# led_2.net
KiCad netlist of a schematic drawn in EAGLE
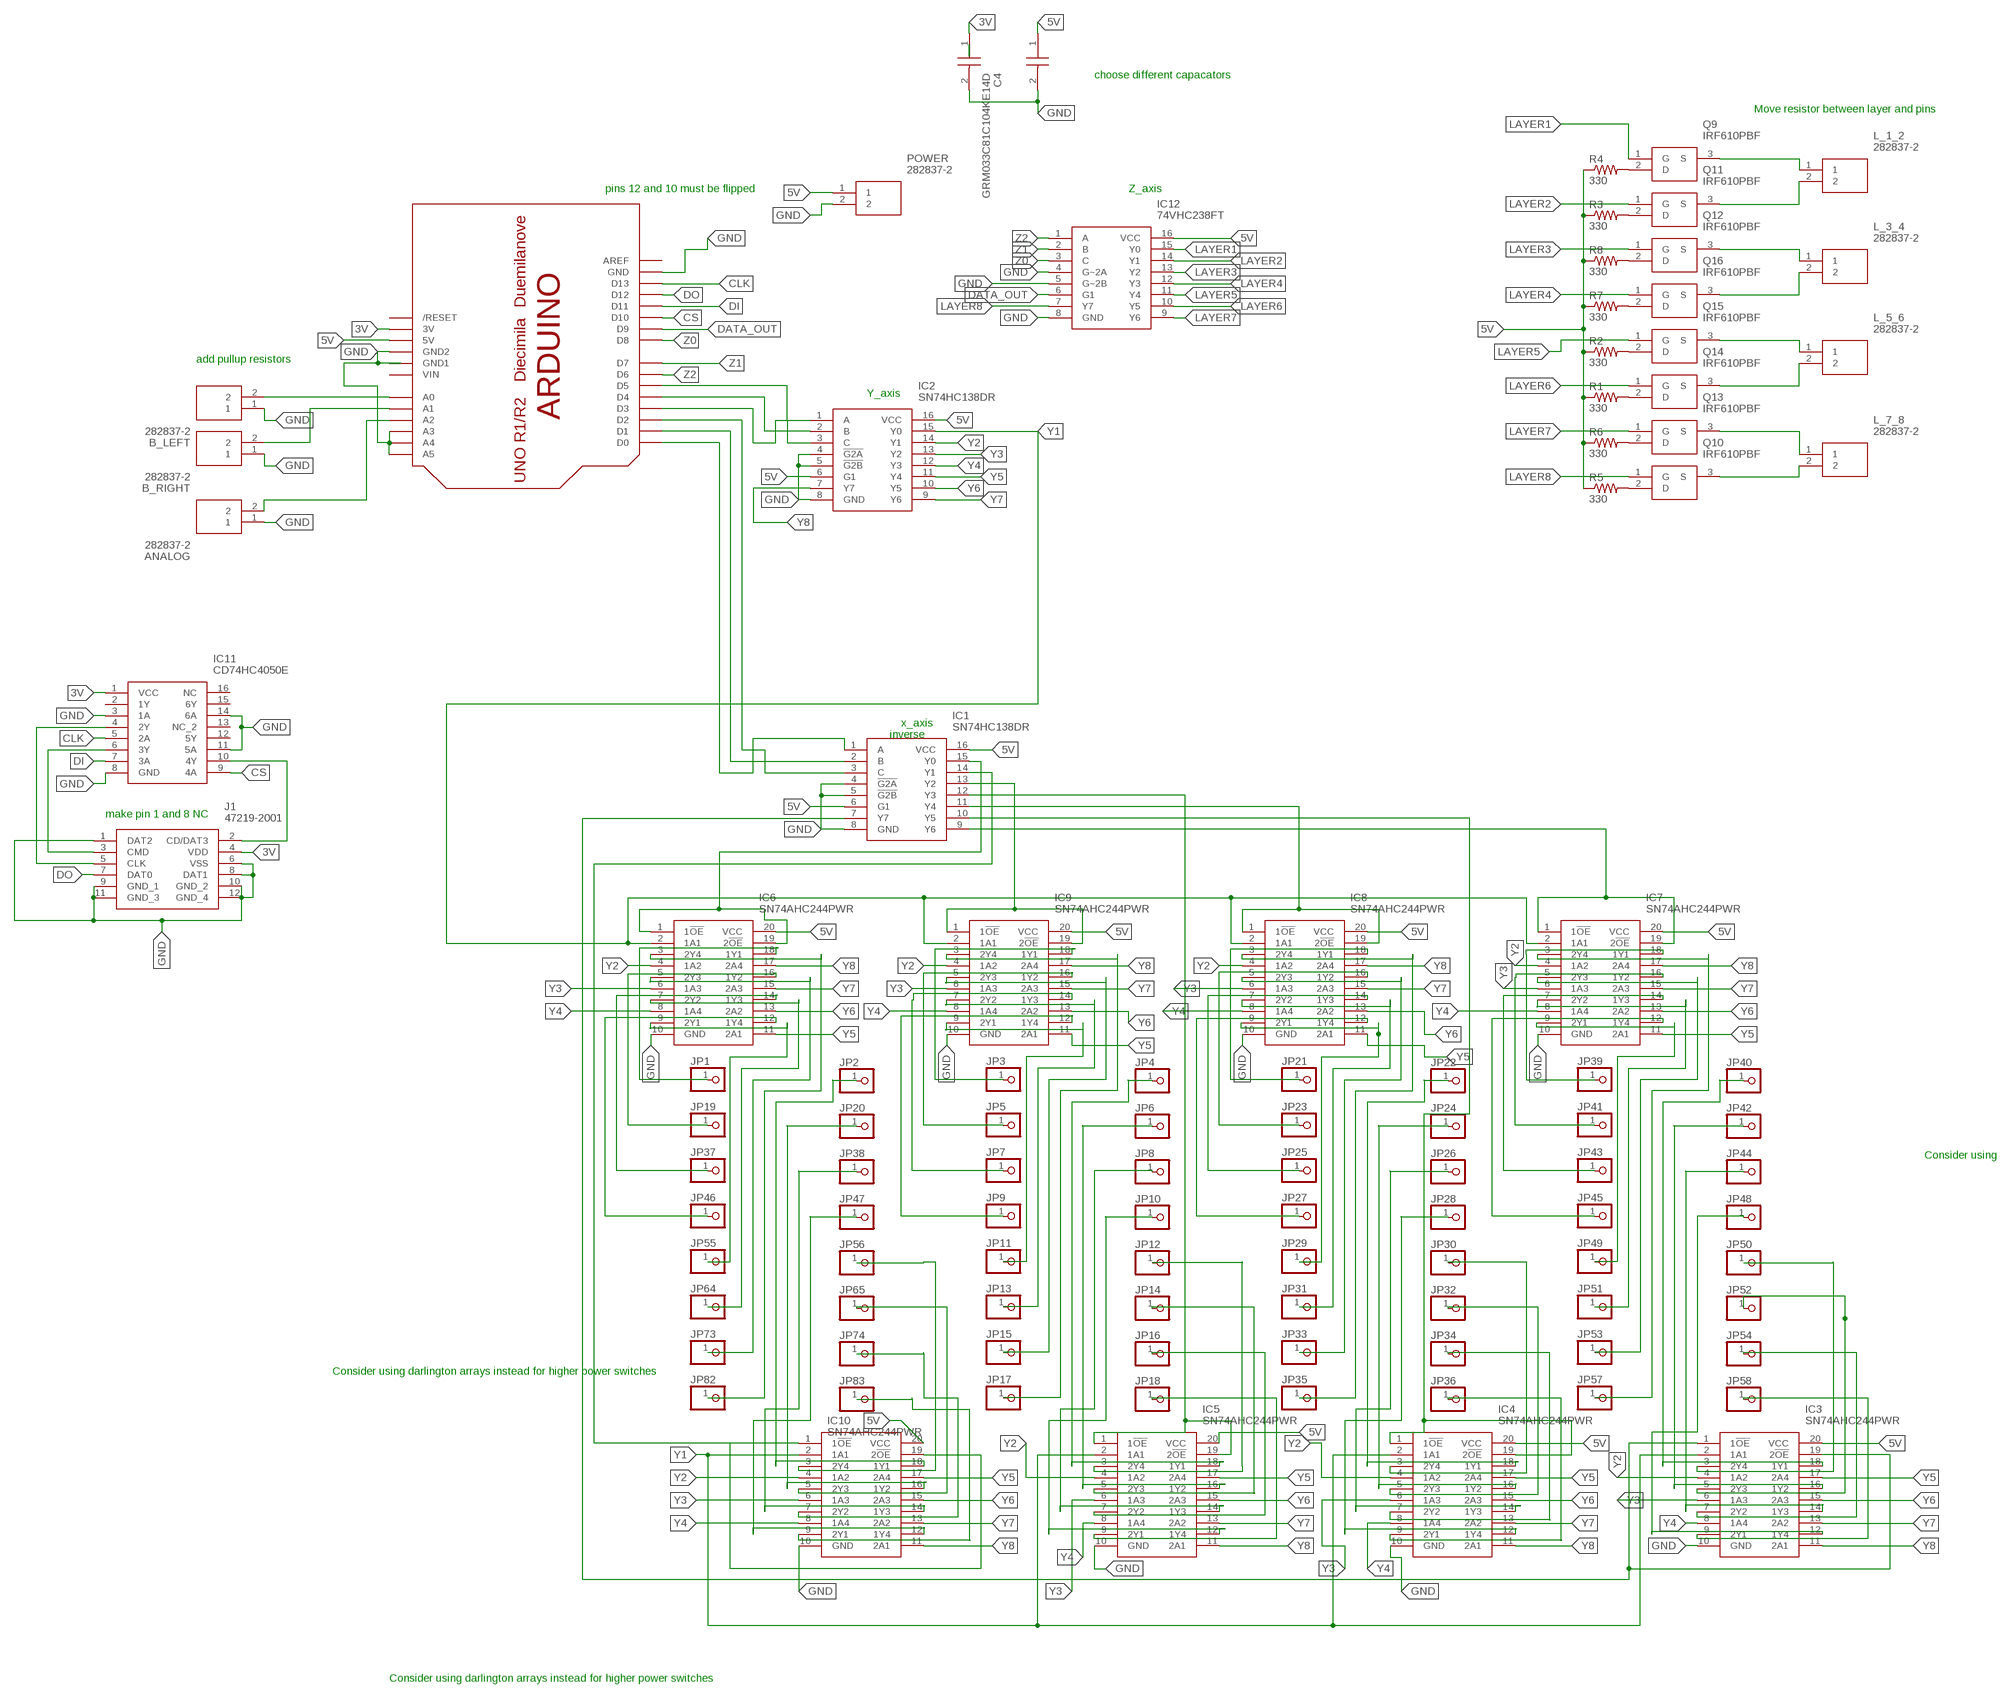
[diagram p0: schematic, sheet 1, part 1 of 2]
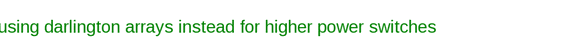
[diagram p1: schematic, sheet 1, part 2 of 2]

(export (version "E")
  (design (tool "Eeschema 10.0.6"))
  (components
    (comp (ref "ANALOG")
      (value "282837-2")
      (footprint "eagle-import:SHDR2W100P0X508_1X2_1016X820X1")
      (fields (field (name "MOUSER_PART_NUMBER") "571-2828372"))
      (libsource (lib "eagle-import") (part "282837-2"))
    )
    (comp (ref "B_LEFT")
      (value "282837-2")
      (footprint "eagle-import:SHDR2W100P0X508_1X2_1016X820X1")
      (fields (field (name "MOUSER_PART_NUMBER") "571-2828372"))
      (libsource (lib "eagle-import") (part "282837-2"))
    )
    (comp (ref "B_RIGHT")
      (value "282837-2")
      (footprint "eagle-import:SHDR2W100P0X508_1X2_1016X820X1")
      (fields (field (name "MOUSER_PART_NUMBER") "571-2828372"))
      (libsource (lib "eagle-import") (part "282837-2"))
    )
    (comp (ref "C4")
      (value "GRM033C81C104KE14D")
      (footprint "eagle-import:CAPC0603X33N")
      (fields (field (name "MOUSER_PART_NUMBER") "81-GRM033C81C104KE4D"))
      (libsource (lib "eagle-import") (part "GRM033C81C104KE14D"))
    )
    (comp (ref "C5")
      (value "GRM033C81C104KE14D")
      (footprint "eagle-import:CAPC0603X33N")
      (fields (field (name "MOUSER_PART_NUMBER") "81-GRM033C81C104KE4D"))
      (libsource (lib "eagle-import") (part "GRM033C81C104KE14D"))
    )
    (comp (ref "IC1")
      (value "SN74HC138DR")
      (footprint "eagle-import:SOIC127P600X175-16N")
      (fields (field (name "MOUSER_PART_NUMBER") "595-SN74HC138DR"))
      (libsource (lib "eagle-import") (part "SN74HC138DR"))
    )
    (comp (ref "IC2")
      (value "SN74HC138DR")
      (footprint "eagle-import:SOIC127P600X175-16N")
      (fields (field (name "MOUSER_PART_NUMBER") "595-SN74HC138DR"))
      (libsource (lib "eagle-import") (part "SN74HC138DR"))
    )
    (comp (ref "IC3")
      (value "SN74AHC244PWR")
      (footprint "eagle-import:SOP65P640X120-20N")
      (fields (field (name "MOUSER_PART_NUMBER") "595-SN74AHC244PWR"))
      (libsource (lib "eagle-import") (part "SN74AHC244PWR"))
    )
    (comp (ref "IC4")
      (value "SN74AHC244PWR")
      (footprint "eagle-import:SOP65P640X120-20N")
      (fields (field (name "MOUSER_PART_NUMBER") "595-SN74AHC244PWR"))
      (libsource (lib "eagle-import") (part "SN74AHC244PWR"))
    )
    (comp (ref "IC5")
      (value "SN74AHC244PWR")
      (footprint "eagle-import:SOP65P640X120-20N")
      (fields (field (name "MOUSER_PART_NUMBER") "595-SN74AHC244PWR"))
      (libsource (lib "eagle-import") (part "SN74AHC244PWR"))
    )
    (comp (ref "IC6")
      (value "SN74AHC244PWR")
      (footprint "eagle-import:SOP65P640X120-20N")
      (fields (field (name "MOUSER_PART_NUMBER") "595-SN74AHC244PWR"))
      (libsource (lib "eagle-import") (part "SN74AHC244PWR"))
    )
    (comp (ref "IC7")
      (value "SN74AHC244PWR")
      (footprint "eagle-import:SOP65P640X120-20N")
      (fields (field (name "MOUSER_PART_NUMBER") "595-SN74AHC244PWR"))
      (libsource (lib "eagle-import") (part "SN74AHC244PWR"))
    )
    (comp (ref "IC8")
      (value "SN74AHC244PWR")
      (footprint "eagle-import:SOP65P640X120-20N")
      (fields (field (name "MOUSER_PART_NUMBER") "595-SN74AHC244PWR"))
      (libsource (lib "eagle-import") (part "SN74AHC244PWR"))
    )
    (comp (ref "IC9")
      (value "SN74AHC244PWR")
      (footprint "eagle-import:SOP65P640X120-20N")
      (fields (field (name "MOUSER_PART_NUMBER") "595-SN74AHC244PWR"))
      (libsource (lib "eagle-import") (part "SN74AHC244PWR"))
    )
    (comp (ref "IC10")
      (value "SN74AHC244PWR")
      (footprint "eagle-import:SOP65P640X120-20N")
      (fields (field (name "MOUSER_PART_NUMBER") "595-SN74AHC244PWR"))
      (libsource (lib "eagle-import") (part "SN74AHC244PWR"))
    )
    (comp (ref "IC11")
      (value "CD74HC4050E")
      (footprint "eagle-import:DIP254P762X508-16")
      (fields (field (name "MOUSER_PART_NUMBER") "595-CD74HC4050E"))
      (libsource (lib "eagle-import") (part "CD74HC4050E"))
    )
    (comp (ref "IC12")
      (value "74VHC238FT")
      (footprint "eagle-import:SOP65P640X120-16N")
      (libsource (lib "eagle-import") (part "74VHC238FT"))
    )
    (comp (ref "J1")
      (value "47219-2001")
      (footprint "eagle-import:472192001")
      (fields (field (name "MOUSER_PART_NUMBER") "538-47219-2001"))
      (libsource (lib "eagle-import") (part "47219-2001"))
    )
    (comp (ref "JP1")
      (value "PINHD-1X1")
      (footprint "eagle-import:1X01")
      (libsource (lib "eagle-import") (part "PINHD-1X1"))
    )
    (comp (ref "JP2")
      (value "PINHD-1X1")
      (footprint "eagle-import:1X01")
      (libsource (lib "eagle-import") (part "PINHD-1X1"))
    )
    (comp (ref "JP3")
      (value "PINHD-1X1")
      (footprint "eagle-import:1X01")
      (libsource (lib "eagle-import") (part "PINHD-1X1"))
    )
    (comp (ref "JP4")
      (value "PINHD-1X1")
      (footprint "eagle-import:1X01")
      (libsource (lib "eagle-import") (part "PINHD-1X1"))
    )
    (comp (ref "JP5")
      (value "PINHD-1X1")
      (footprint "eagle-import:1X01")
      (libsource (lib "eagle-import") (part "PINHD-1X1"))
    )
    (comp (ref "JP6")
      (value "PINHD-1X1")
      (footprint "eagle-import:1X01")
      (libsource (lib "eagle-import") (part "PINHD-1X1"))
    )
    (comp (ref "JP7")
      (value "PINHD-1X1")
      (footprint "eagle-import:1X01")
      (libsource (lib "eagle-import") (part "PINHD-1X1"))
    )
    (comp (ref "JP8")
      (value "PINHD-1X1")
      (footprint "eagle-import:1X01")
      (libsource (lib "eagle-import") (part "PINHD-1X1"))
    )
    (comp (ref "JP9")
      (value "PINHD-1X1")
      (footprint "eagle-import:1X01")
      (libsource (lib "eagle-import") (part "PINHD-1X1"))
    )
    (comp (ref "JP10")
      (value "PINHD-1X1")
      (footprint "eagle-import:1X01")
      (libsource (lib "eagle-import") (part "PINHD-1X1"))
    )
    (comp (ref "JP11")
      (value "PINHD-1X1")
      (footprint "eagle-import:1X01")
      (libsource (lib "eagle-import") (part "PINHD-1X1"))
    )
    (comp (ref "JP12")
      (value "PINHD-1X1")
      (footprint "eagle-import:1X01")
      (libsource (lib "eagle-import") (part "PINHD-1X1"))
    )
    (comp (ref "JP13")
      (value "PINHD-1X1")
      (footprint "eagle-import:1X01")
      (libsource (lib "eagle-import") (part "PINHD-1X1"))
    )
    (comp (ref "JP14")
      (value "PINHD-1X1")
      (footprint "eagle-import:1X01")
      (libsource (lib "eagle-import") (part "PINHD-1X1"))
    )
    (comp (ref "JP15")
      (value "PINHD-1X1")
      (footprint "eagle-import:1X01")
      (libsource (lib "eagle-import") (part "PINHD-1X1"))
    )
    (comp (ref "JP16")
      (value "PINHD-1X1")
      (footprint "eagle-import:1X01")
      (libsource (lib "eagle-import") (part "PINHD-1X1"))
    )
    (comp (ref "JP17")
      (value "PINHD-1X1")
      (footprint "eagle-import:1X01")
      (libsource (lib "eagle-import") (part "PINHD-1X1"))
    )
    (comp (ref "JP18")
      (value "PINHD-1X1")
      (footprint "eagle-import:1X01")
      (libsource (lib "eagle-import") (part "PINHD-1X1"))
    )
    (comp (ref "JP19")
      (value "PINHD-1X1")
      (footprint "eagle-import:1X01")
      (libsource (lib "eagle-import") (part "PINHD-1X1"))
    )
    (comp (ref "JP20")
      (value "PINHD-1X1")
      (footprint "eagle-import:1X01")
      (libsource (lib "eagle-import") (part "PINHD-1X1"))
    )
    (comp (ref "JP21")
      (value "PINHD-1X1")
      (footprint "eagle-import:1X01")
      (libsource (lib "eagle-import") (part "PINHD-1X1"))
    )
    (comp (ref "JP22")
      (value "PINHD-1X1")
      (footprint "eagle-import:1X01")
      (libsource (lib "eagle-import") (part "PINHD-1X1"))
    )
    (comp (ref "JP23")
      (value "PINHD-1X1")
      (footprint "eagle-import:1X01")
      (libsource (lib "eagle-import") (part "PINHD-1X1"))
    )
    (comp (ref "JP24")
      (value "PINHD-1X1")
      (footprint "eagle-import:1X01")
      (libsource (lib "eagle-import") (part "PINHD-1X1"))
    )
    (comp (ref "JP25")
      (value "PINHD-1X1")
      (footprint "eagle-import:1X01")
      (libsource (lib "eagle-import") (part "PINHD-1X1"))
    )
    (comp (ref "JP26")
      (value "PINHD-1X1")
      (footprint "eagle-import:1X01")
      (libsource (lib "eagle-import") (part "PINHD-1X1"))
    )
    (comp (ref "JP27")
      (value "PINHD-1X1")
      (footprint "eagle-import:1X01")
      (libsource (lib "eagle-import") (part "PINHD-1X1"))
    )
    (comp (ref "JP28")
      (value "PINHD-1X1")
      (footprint "eagle-import:1X01")
      (libsource (lib "eagle-import") (part "PINHD-1X1"))
    )
    (comp (ref "JP29")
      (value "PINHD-1X1")
      (footprint "eagle-import:1X01")
      (libsource (lib "eagle-import") (part "PINHD-1X1"))
    )
    (comp (ref "JP30")
      (value "PINHD-1X1")
      (footprint "eagle-import:1X01")
      (libsource (lib "eagle-import") (part "PINHD-1X1"))
    )
    (comp (ref "JP31")
      (value "PINHD-1X1")
      (footprint "eagle-import:1X01")
      (libsource (lib "eagle-import") (part "PINHD-1X1"))
    )
    (comp (ref "JP32")
      (value "PINHD-1X1")
      (footprint "eagle-import:1X01")
      (libsource (lib "eagle-import") (part "PINHD-1X1"))
    )
    (comp (ref "JP33")
      (value "PINHD-1X1")
      (footprint "eagle-import:1X01")
      (libsource (lib "eagle-import") (part "PINHD-1X1"))
    )
    (comp (ref "JP34")
      (value "PINHD-1X1")
      (footprint "eagle-import:1X01")
      (libsource (lib "eagle-import") (part "PINHD-1X1"))
    )
    (comp (ref "JP35")
      (value "PINHD-1X1")
      (footprint "eagle-import:1X01")
      (libsource (lib "eagle-import") (part "PINHD-1X1"))
    )
    (comp (ref "JP36")
      (value "PINHD-1X1")
      (footprint "eagle-import:1X01")
      (libsource (lib "eagle-import") (part "PINHD-1X1"))
    )
    (comp (ref "JP37")
      (value "PINHD-1X1")
      (footprint "eagle-import:1X01")
      (libsource (lib "eagle-import") (part "PINHD-1X1"))
    )
    (comp (ref "JP38")
      (value "PINHD-1X1")
      (footprint "eagle-import:1X01")
      (libsource (lib "eagle-import") (part "PINHD-1X1"))
    )
    (comp (ref "JP39")
      (value "PINHD-1X1")
      (footprint "eagle-import:1X01")
      (libsource (lib "eagle-import") (part "PINHD-1X1"))
    )
    (comp (ref "JP40")
      (value "PINHD-1X1")
      (footprint "eagle-import:1X01")
      (libsource (lib "eagle-import") (part "PINHD-1X1"))
    )
    (comp (ref "JP41")
      (value "PINHD-1X1")
      (footprint "eagle-import:1X01")
      (libsource (lib "eagle-import") (part "PINHD-1X1"))
    )
    (comp (ref "JP42")
      (value "PINHD-1X1")
      (footprint "eagle-import:1X01")
      (libsource (lib "eagle-import") (part "PINHD-1X1"))
    )
    (comp (ref "JP43")
      (value "PINHD-1X1")
      (footprint "eagle-import:1X01")
      (libsource (lib "eagle-import") (part "PINHD-1X1"))
    )
    (comp (ref "JP44")
      (value "PINHD-1X1")
      (footprint "eagle-import:1X01")
      (libsource (lib "eagle-import") (part "PINHD-1X1"))
    )
    (comp (ref "JP45")
      (value "PINHD-1X1")
      (footprint "eagle-import:1X01")
      (libsource (lib "eagle-import") (part "PINHD-1X1"))
    )
    (comp (ref "JP46")
      (value "PINHD-1X1")
      (footprint "eagle-import:1X01")
      (libsource (lib "eagle-import") (part "PINHD-1X1"))
    )
    (comp (ref "JP47")
      (value "PINHD-1X1")
      (footprint "eagle-import:1X01")
      (libsource (lib "eagle-import") (part "PINHD-1X1"))
    )
    (comp (ref "JP48")
      (value "PINHD-1X1")
      (footprint "eagle-import:1X01")
      (libsource (lib "eagle-import") (part "PINHD-1X1"))
    )
    (comp (ref "JP49")
      (value "PINHD-1X1")
      (footprint "eagle-import:1X01")
      (libsource (lib "eagle-import") (part "PINHD-1X1"))
    )
    (comp (ref "JP50")
      (value "PINHD-1X1")
      (footprint "eagle-import:1X01")
      (libsource (lib "eagle-import") (part "PINHD-1X1"))
    )
    (comp (ref "JP51")
      (value "PINHD-1X1")
      (footprint "eagle-import:1X01")
      (libsource (lib "eagle-import") (part "PINHD-1X1"))
    )
    (comp (ref "JP52")
      (value "PINHD-1X1")
      (footprint "eagle-import:1X01")
      (libsource (lib "eagle-import") (part "PINHD-1X1"))
    )
    (comp (ref "JP53")
      (value "PINHD-1X1")
      (footprint "eagle-import:1X01")
      (libsource (lib "eagle-import") (part "PINHD-1X1"))
    )
    (comp (ref "JP54")
      (value "PINHD-1X1")
      (footprint "eagle-import:1X01")
      (libsource (lib "eagle-import") (part "PINHD-1X1"))
    )
    (comp (ref "JP55")
      (value "PINHD-1X1")
      (footprint "eagle-import:1X01")
      (libsource (lib "eagle-import") (part "PINHD-1X1"))
    )
    (comp (ref "JP56")
      (value "PINHD-1X1")
      (footprint "eagle-import:1X01")
      (libsource (lib "eagle-import") (part "PINHD-1X1"))
    )
    (comp (ref "JP57")
      (value "PINHD-1X1")
      (footprint "eagle-import:1X01")
      (libsource (lib "eagle-import") (part "PINHD-1X1"))
    )
    (comp (ref "JP58")
      (value "PINHD-1X1")
      (footprint "eagle-import:1X01")
      (libsource (lib "eagle-import") (part "PINHD-1X1"))
    )
    (comp (ref "JP64")
      (value "PINHD-1X1")
      (footprint "eagle-import:1X01")
      (libsource (lib "eagle-import") (part "PINHD-1X1"))
    )
    (comp (ref "JP65")
      (value "PINHD-1X1")
      (footprint "eagle-import:1X01")
      (libsource (lib "eagle-import") (part "PINHD-1X1"))
    )
    (comp (ref "JP73")
      (value "PINHD-1X1")
      (footprint "eagle-import:1X01")
      (libsource (lib "eagle-import") (part "PINHD-1X1"))
    )
    (comp (ref "JP74")
      (value "PINHD-1X1")
      (footprint "eagle-import:1X01")
      (libsource (lib "eagle-import") (part "PINHD-1X1"))
    )
    (comp (ref "JP82")
      (value "PINHD-1X1")
      (footprint "eagle-import:1X01")
      (libsource (lib "eagle-import") (part "PINHD-1X1"))
    )
    (comp (ref "JP83")
      (value "PINHD-1X1")
      (footprint "eagle-import:1X01")
      (libsource (lib "eagle-import") (part "PINHD-1X1"))
    )
    (comp (ref "L_1_2")
      (value "282837-2")
      (footprint "eagle-import:SHDR2W100P0X508_1X2_1016X820X1")
      (fields (field (name "MOUSER_PART_NUMBER") "571-2828372"))
      (libsource (lib "eagle-import") (part "282837-2"))
    )
    (comp (ref "L_3_4")
      (value "282837-2")
      (footprint "eagle-import:SHDR2W100P0X508_1X2_1016X820X1")
      (fields (field (name "MOUSER_PART_NUMBER") "571-2828372"))
      (libsource (lib "eagle-import") (part "282837-2"))
    )
    (comp (ref "L_5_6")
      (value "282837-2")
      (footprint "eagle-import:SHDR2W100P0X508_1X2_1016X820X1")
      (fields (field (name "MOUSER_PART_NUMBER") "571-2828372"))
      (libsource (lib "eagle-import") (part "282837-2"))
    )
    (comp (ref "L_7_8")
      (value "282837-2")
      (footprint "eagle-import:SHDR2W100P0X508_1X2_1016X820X1")
      (fields (field (name "MOUSER_PART_NUMBER") "571-2828372"))
      (libsource (lib "eagle-import") (part "282837-2"))
    )
    (comp (ref "POWER")
      (value "282837-2")
      (footprint "eagle-import:SHDR2W100P0X508_1X2_1016X820X1")
      (fields (field (name "MOUSER_PART_NUMBER") "571-2828372"))
      (libsource (lib "eagle-import") (part "282837-2"))
    )
    (comp (ref "Q9")
      (value "IRF610PBF")
      (footprint "eagle-import:TO254P465X1024X2050-3P")
      (fields (field (name "MOUSER_PART_NUMBER") "844-IRF610PBF"))
      (libsource (lib "eagle-import") (part "IRF610PBF"))
    )
    (comp (ref "Q10")
      (value "IRF610PBF")
      (footprint "eagle-import:TO254P465X1024X2050-3P")
      (fields (field (name "MOUSER_PART_NUMBER") "844-IRF610PBF"))
      (libsource (lib "eagle-import") (part "IRF610PBF"))
    )
    (comp (ref "Q11")
      (value "IRF610PBF")
      (footprint "eagle-import:TO254P465X1024X2050-3P")
      (fields (field (name "MOUSER_PART_NUMBER") "844-IRF610PBF"))
      (libsource (lib "eagle-import") (part "IRF610PBF"))
    )
    (comp (ref "Q12")
      (value "IRF610PBF")
      (footprint "eagle-import:TO254P465X1024X2050-3P")
      (fields (field (name "MOUSER_PART_NUMBER") "844-IRF610PBF"))
      (libsource (lib "eagle-import") (part "IRF610PBF"))
    )
    (comp (ref "Q13")
      (value "IRF610PBF")
      (footprint "eagle-import:TO254P465X1024X2050-3P")
      (fields (field (name "MOUSER_PART_NUMBER") "844-IRF610PBF"))
      (libsource (lib "eagle-import") (part "IRF610PBF"))
    )
    (comp (ref "Q14")
      (value "IRF610PBF")
      (footprint "eagle-import:TO254P465X1024X2050-3P")
      (fields (field (name "MOUSER_PART_NUMBER") "844-IRF610PBF"))
      (libsource (lib "eagle-import") (part "IRF610PBF"))
    )
    (comp (ref "Q15")
      (value "IRF610PBF")
      (footprint "eagle-import:TO254P465X1024X2050-3P")
      (fields (field (name "MOUSER_PART_NUMBER") "844-IRF610PBF"))
      (libsource (lib "eagle-import") (part "IRF610PBF"))
    )
    (comp (ref "Q16")
      (value "IRF610PBF")
      (footprint "eagle-import:TO254P465X1024X2050-3P")
      (fields (field (name "MOUSER_PART_NUMBER") "844-IRF610PBF"))
      (libsource (lib "eagle-import") (part "IRF610PBF"))
    )
    (comp (ref "R1")
      (value "330")
      (footprint "eagle-import:0207_12")
      (libsource (lib "eagle-import") (part "R-US_0207/12"))
    )
    (comp (ref "R2")
      (value "330")
      (footprint "eagle-import:0207_12")
      (libsource (lib "eagle-import") (part "R-US_0207/12"))
    )
    (comp (ref "R3")
      (value "330")
      (footprint "eagle-import:0207_12")
      (libsource (lib "eagle-import") (part "R-US_0207/12"))
    )
    (comp (ref "R4")
      (value "330")
      (footprint "eagle-import:0207_12")
      (libsource (lib "eagle-import") (part "R-US_0207/12"))
    )
    (comp (ref "R5")
      (value "330")
      (footprint "eagle-import:0207_12")
      (libsource (lib "eagle-import") (part "R-US_0207/12"))
    )
    (comp (ref "R6")
      (value "330")
      (footprint "eagle-import:0207_12")
      (libsource (lib "eagle-import") (part "R-US_0207/12"))
    )
    (comp (ref "R7")
      (value "330")
      (footprint "eagle-import:0207_12")
      (libsource (lib "eagle-import") (part "R-US_0207/12"))
    )
    (comp (ref "R8")
      (value "330")
      (footprint "eagle-import:0207_12")
      (libsource (lib "eagle-import") (part "R-US_0207/12"))
    )
    (comp (ref "U$2")
      (value "ARDUINO-NOHOLE")
      (footprint "eagle-import:ARDUINO-NOHOLE")
      (libsource (lib "eagle-import") (part "ARDUINO-NOHOLE"))
    )
  )
  (nets
    (net (code "1") (name "/VIN") (class "Default")
      (node (ref "U$2") (pin "VIN") (pinfunction "VIN_VIN") (pintype "power_in"))
    )
    (net (code "2") (name "3V") (class "Default")
      (node (ref "C4") (pin "1") (pinfunction "1_1") (pintype "bidirectional"))
      (node (ref "IC11") (pin "1") (pinfunction "VCC_1") (pintype "bidirectional"))
      (node (ref "J1") (pin "4") (pinfunction "VDD_4") (pintype "bidirectional"))
      (node (ref "U$2") (pin "3V") (pinfunction "3V_3V") (pintype "power_in"))
    )
    (net (code "3") (name "5V") (class "Default")
      (node (ref "C5") (pin "1") (pinfunction "1_1") (pintype "bidirectional"))
      (node (ref "IC1") (pin "16") (pinfunction "VCC_16") (pintype "power_in"))
      (node (ref "IC1") (pin "6") (pinfunction "G1_6") (pintype "bidirectional"))
      (node (ref "IC10") (pin "20") (pinfunction "VCC_20") (pintype "bidirectional"))
      (node (ref "IC12") (pin "16") (pinfunction "VCC_16") (pintype "power_in"))
      (node (ref "IC2") (pin "16") (pinfunction "VCC_16") (pintype "power_in"))
      (node (ref "IC2") (pin "6") (pinfunction "G1_6") (pintype "bidirectional"))
      (node (ref "IC3") (pin "20") (pinfunction "VCC_20") (pintype "bidirectional"))
      (node (ref "IC4") (pin "20") (pinfunction "VCC_20") (pintype "bidirectional"))
      (node (ref "IC5") (pin "20") (pinfunction "VCC_20") (pintype "bidirectional"))
      (node (ref "IC6") (pin "20") (pinfunction "VCC_20") (pintype "bidirectional"))
      (node (ref "IC7") (pin "20") (pinfunction "VCC_20") (pintype "bidirectional"))
      (node (ref "IC8") (pin "20") (pinfunction "VCC_20") (pintype "bidirectional"))
      (node (ref "IC9") (pin "20") (pinfunction "VCC_20") (pintype "bidirectional"))
      (node (ref "POWER") (pin "1") (pinfunction "1_1") (pintype "bidirectional"))
      (node (ref "R1") (pin "1") (pinfunction "1_1") (pintype "passive"))
      (node (ref "R2") (pin "1") (pinfunction "1_1") (pintype "passive"))
      (node (ref "R3") (pin "1") (pinfunction "1_1") (pintype "passive"))
      (node (ref "R4") (pin "1") (pinfunction "1_1") (pintype "passive"))
      (node (ref "R5") (pin "1") (pinfunction "1_1") (pintype "passive"))
      (node (ref "R6") (pin "1") (pinfunction "1_1") (pintype "passive"))
      (node (ref "R7") (pin "1") (pinfunction "1_1") (pintype "passive"))
      (node (ref "R8") (pin "1") (pinfunction "1_1") (pintype "passive"))
      (node (ref "U$2") (pin "5V") (pinfunction "5V_5V") (pintype "power_in"))
    )
    (net (code "4") (name "CLK") (class "Default")
      (node (ref "IC11") (pin "5") (pinfunction "2A_5") (pintype "bidirectional"))
      (node (ref "U$2") (pin "D13") (pinfunction "D13_D13") (pintype "bidirectional"))
    )
    (net (code "5") (name "CS") (class "Default")
      (node (ref "IC11") (pin "9") (pinfunction "4A_9") (pintype "bidirectional"))
      (node (ref "U$2") (pin "D10") (pinfunction "D10_D10") (pintype "bidirectional"))
    )
    (net (code "6") (name "DATA_OUT") (class "Default")
      (node (ref "IC12") (pin "6") (pinfunction "G1_6") (pintype "input"))
      (node (ref "U$2") (pin "D9") (pinfunction "D9_D9") (pintype "bidirectional"))
    )
    (net (code "7") (name "DI") (class "Default")
      (node (ref "IC11") (pin "7") (pinfunction "3A_7") (pintype "bidirectional"))
      (node (ref "U$2") (pin "D11") (pinfunction "D11_D11") (pintype "bidirectional"))
    )
    (net (code "8") (name "DO") (class "Default")
      (node (ref "J1") (pin "7") (pinfunction "DAT0_7") (pintype "bidirectional"))
      (node (ref "U$2") (pin "D12") (pinfunction "D12_D12") (pintype "bidirectional"))
    )
    (net (code "9") (name "GND") (class "Default")
      (node (ref "ANALOG") (pin "1") (pinfunction "1_1") (pintype "bidirectional"))
      (node (ref "B_LEFT") (pin "1") (pinfunction "1_1") (pintype "bidirectional"))
      (node (ref "B_RIGHT") (pin "1") (pinfunction "1_1") (pintype "bidirectional"))
      (node (ref "C4") (pin "2") (pinfunction "2_2") (pintype "bidirectional"))
      (node (ref "C5") (pin "2") (pinfunction "2_2") (pintype "bidirectional"))
      (node (ref "IC1") (pin "4") (pinfunction "~{G2A}_4") (pintype "bidirectional"))
      (node (ref "IC1") (pin "5") (pinfunction "~{G2B}_5") (pintype "bidirectional"))
      (node (ref "IC1") (pin "8") (pinfunction "GND_8") (pintype "power_in"))
      (node (ref "IC10") (pin "10") (pinfunction "GND_10") (pintype "bidirectional"))
      (node (ref "IC11") (pin "11") (pinfunction "5A_11") (pintype "bidirectional"))
      (node (ref "IC11") (pin "14") (pinfunction "6A_14") (pintype "bidirectional"))
      (node (ref "IC11") (pin "3") (pinfunction "1A_3") (pintype "bidirectional"))
      (node (ref "IC11") (pin "8") (pinfunction "GND_8") (pintype "bidirectional"))
      (node (ref "IC12") (pin "4") (pinfunction "G~{2A}_4") (pintype "input"))
      (node (ref "IC12") (pin "5") (pinfunction "G~{2B}_5") (pintype "input"))
      (node (ref "IC12") (pin "8") (pinfunction "GND_8") (pintype "power_in"))
      (node (ref "IC2") (pin "4") (pinfunction "~{G2A}_4") (pintype "bidirectional"))
      (node (ref "IC2") (pin "5") (pinfunction "~{G2B}_5") (pintype "bidirectional"))
      (node (ref "IC2") (pin "8") (pinfunction "GND_8") (pintype "power_in"))
      (node (ref "IC3") (pin "10") (pinfunction "GND_10") (pintype "bidirectional"))
      (node (ref "IC4") (pin "10") (pinfunction "GND_10") (pintype "bidirectional"))
      (node (ref "IC5") (pin "10") (pinfunction "GND_10") (pintype "bidirectional"))
      (node (ref "IC6") (pin "10") (pinfunction "GND_10") (pintype "bidirectional"))
      (node (ref "IC7") (pin "10") (pinfunction "GND_10") (pintype "bidirectional"))
      (node (ref "IC8") (pin "10") (pinfunction "GND_10") (pintype "bidirectional"))
      (node (ref "IC9") (pin "10") (pinfunction "GND_10") (pintype "bidirectional"))
      (node (ref "J1") (pin "1") (pinfunction "DAT2_1") (pintype "bidirectional"))
      (node (ref "J1") (pin "10") (pinfunction "GND_2_10") (pintype "bidirectional"))
      (node (ref "J1") (pin "11") (pinfunction "GND_3_11") (pintype "bidirectional"))
      (node (ref "J1") (pin "12") (pinfunction "GND_4_12") (pintype "bidirectional"))
      (node (ref "J1") (pin "6") (pinfunction "VSS_6") (pintype "bidirectional"))
      (node (ref "J1") (pin "8") (pinfunction "DAT1_8") (pintype "bidirectional"))
      (node (ref "J1") (pin "9") (pinfunction "GND_1_9") (pintype "bidirectional"))
      (node (ref "POWER") (pin "2") (pinfunction "2_2") (pintype "bidirectional"))
      (node (ref "U$2") (pin "A3") (pinfunction "A3_A3") (pintype "bidirectional"))
      (node (ref "U$2") (pin "A4") (pinfunction "A4_A4") (pintype "bidirectional"))
      (node (ref "U$2") (pin "A5") (pinfunction "A5_A5") (pintype "bidirectional"))
      (node (ref "U$2") (pin "GND") (pinfunction "GND_GND") (pintype "power_in"))
      (node (ref "U$2") (pin "GND1") (pinfunction "GND1_GND1") (pintype "power_in"))
      (node (ref "U$2") (pin "GND2") (pinfunction "GND2_GND2") (pintype "power_in"))
    )
    (net (code "10") (name "LAYER1") (class "Default")
      (node (ref "IC12") (pin "15") (pinfunction "Y0_15") (pintype "output"))
      (node (ref "Q9") (pin "1") (pinfunction "G_1") (pintype "bidirectional"))
    )
    (net (code "11") (name "LAYER2") (class "Default")
      (node (ref "IC12") (pin "14") (pinfunction "Y1_14") (pintype "output"))
      (node (ref "Q11") (pin "1") (pinfunction "G_1") (pintype "bidirectional"))
    )
    (net (code "12") (name "LAYER3") (class "Default")
      (node (ref "IC12") (pin "13") (pinfunction "Y2_13") (pintype "output"))
      (node (ref "Q12") (pin "1") (pinfunction "G_1") (pintype "bidirectional"))
    )
    (net (code "13") (name "LAYER4") (class "Default")
      (node (ref "IC12") (pin "12") (pinfunction "Y3_12") (pintype "output"))
      (node (ref "Q16") (pin "1") (pinfunction "G_1") (pintype "bidirectional"))
    )
    (net (code "14") (name "LAYER5") (class "Default")
      (node (ref "IC12") (pin "11") (pinfunction "Y4_11") (pintype "output"))
      (node (ref "Q15") (pin "1") (pinfunction "G_1") (pintype "bidirectional"))
    )
    (net (code "15") (name "LAYER6") (class "Default")
      (node (ref "IC12") (pin "10") (pinfunction "Y5_10") (pintype "output"))
      (node (ref "Q14") (pin "1") (pinfunction "G_1") (pintype "bidirectional"))
    )
    (net (code "16") (name "LAYER7") (class "Default")
      (node (ref "IC12") (pin "9") (pinfunction "Y6_9") (pintype "output"))
      (node (ref "Q13") (pin "1") (pinfunction "G_1") (pintype "bidirectional"))
    )
    (net (code "17") (name "LAYER8") (class "Default")
      (node (ref "IC12") (pin "7") (pinfunction "Y7_7") (pintype "output"))
      (node (ref "Q10") (pin "1") (pinfunction "G_1") (pintype "bidirectional"))
    )
    (net (code "18") (name "Net-(ANALOG-Pad2)") (class "Default")
      (node (ref "ANALOG") (pin "2") (pinfunction "2_2") (pintype "bidirectional"))
      (node (ref "U$2") (pin "A2") (pinfunction "A2_A2") (pintype "bidirectional"))
    )
    (net (code "19") (name "Net-(B_LEFT-Pad2)") (class "Default")
      (node (ref "B_LEFT") (pin "2") (pinfunction "2_2") (pintype "bidirectional"))
      (node (ref "U$2") (pin "A0") (pinfunction "A0_A0") (pintype "bidirectional"))
    )
    (net (code "20") (name "Net-(B_RIGHT-Pad2)") (class "Default")
      (node (ref "B_RIGHT") (pin "2") (pinfunction "2_2") (pintype "bidirectional"))
      (node (ref "U$2") (pin "A1") (pinfunction "A1_A1") (pintype "bidirectional"))
    )
    (net (code "21") (name "Net-(IC1-A)") (class "Default")
      (node (ref "IC1") (pin "1") (pinfunction "A_1") (pintype "bidirectional"))
      (node (ref "U$2") (pin "D0") (pinfunction "D0_D0") (pintype "bidirectional"))
    )
    (net (code "22") (name "Net-(IC1-B)") (class "Default")
      (node (ref "IC1") (pin "2") (pinfunction "B_2") (pintype "bidirectional"))
      (node (ref "U$2") (pin "D1") (pinfunction "D1_D1") (pintype "bidirectional"))
    )
    (net (code "23") (name "Net-(IC1-C)") (class "Default")
      (node (ref "IC1") (pin "3") (pinfunction "C_3") (pintype "bidirectional"))
      (node (ref "U$2") (pin "D2") (pinfunction "D2_D2") (pintype "bidirectional"))
    )
    (net (code "24") (name "Net-(IC1-Y0)") (class "Default")
      (node (ref "IC1") (pin "15") (pinfunction "Y0_15") (pintype "bidirectional"))
      (node (ref "IC6") (pin "1") (pinfunction "1~{OE}_1") (pintype "bidirectional"))
      (node (ref "IC6") (pin "19") (pinfunction "2~{OE}_19") (pintype "bidirectional"))
    )
    (net (code "25") (name "Net-(IC1-Y1)") (class "Default")
      (node (ref "IC1") (pin "14") (pinfunction "Y1_14") (pintype "bidirectional"))
      (node (ref "IC10") (pin "1") (pinfunction "1~{OE}_1") (pintype "bidirectional"))
      (node (ref "IC10") (pin "19") (pinfunction "2~{OE}_19") (pintype "bidirectional"))
    )
    (net (code "26") (name "Net-(IC1-Y2)") (class "Default")
      (node (ref "IC1") (pin "13") (pinfunction "Y2_13") (pintype "bidirectional"))
      (node (ref "IC9") (pin "1") (pinfunction "1~{OE}_1") (pintype "bidirectional"))
      (node (ref "IC9") (pin "19") (pinfunction "2~{OE}_19") (pintype "bidirectional"))
    )
    (net (code "27") (name "Net-(IC1-Y3)") (class "Default")
      (node (ref "IC1") (pin "12") (pinfunction "Y3_12") (pintype "bidirectional"))
      (node (ref "IC5") (pin "1") (pinfunction "1~{OE}_1") (pintype "bidirectional"))
      (node (ref "IC5") (pin "19") (pinfunction "2~{OE}_19") (pintype "bidirectional"))
    )
    (net (code "28") (name "Net-(IC1-Y4)") (class "Default")
      (node (ref "IC1") (pin "11") (pinfunction "Y4_11") (pintype "bidirectional"))
      (node (ref "IC8") (pin "1") (pinfunction "1~{OE}_1") (pintype "bidirectional"))
      (node (ref "IC8") (pin "19") (pinfunction "2~{OE}_19") (pintype "bidirectional"))
    )
    (net (code "29") (name "Net-(IC1-Y5)") (class "Default")
      (node (ref "IC1") (pin "10") (pinfunction "Y5_10") (pintype "bidirectional"))
      (node (ref "IC4") (pin "1") (pinfunction "1~{OE}_1") (pintype "bidirectional"))
      (node (ref "IC4") (pin "19") (pinfunction "2~{OE}_19") (pintype "bidirectional"))
    )
    (net (code "30") (name "Net-(IC1-Y6)") (class "Default")
      (node (ref "IC1") (pin "9") (pinfunction "Y6_9") (pintype "bidirectional"))
      (node (ref "IC7") (pin "1") (pinfunction "1~{OE}_1") (pintype "bidirectional"))
      (node (ref "IC7") (pin "19") (pinfunction "2~{OE}_19") (pintype "bidirectional"))
    )
    (net (code "31") (name "Net-(IC1-Y7)") (class "Default")
      (node (ref "IC1") (pin "7") (pinfunction "Y7_7") (pintype "bidirectional"))
      (node (ref "IC3") (pin "1") (pinfunction "1~{OE}_1") (pintype "bidirectional"))
      (node (ref "IC3") (pin "19") (pinfunction "2~{OE}_19") (pintype "bidirectional"))
    )
    (net (code "32") (name "Net-(IC2-A)") (class "Default")
      (node (ref "IC2") (pin "1") (pinfunction "A_1") (pintype "bidirectional"))
      (node (ref "U$2") (pin "D3") (pinfunction "D3_D3") (pintype "bidirectional"))
    )
    (net (code "33") (name "Net-(IC2-B)") (class "Default")
      (node (ref "IC2") (pin "2") (pinfunction "B_2") (pintype "bidirectional"))
      (node (ref "U$2") (pin "D4") (pinfunction "D4_D4") (pintype "bidirectional"))
    )
    (net (code "34") (name "Net-(IC2-C)") (class "Default")
      (node (ref "IC2") (pin "3") (pinfunction "C_3") (pintype "bidirectional"))
      (node (ref "U$2") (pin "D5") (pinfunction "D5_D5") (pintype "bidirectional"))
    )
    (net (code "35") (name "Net-(IC3-1Y1)") (class "Default")
      (node (ref "IC3") (pin "18") (pinfunction "1Y1_18") (pintype "bidirectional"))
      (node (ref "JP40") (pin "1") (pinfunction "1_1") (pintype "passive"))
    )
    (net (code "36") (name "Net-(IC3-1Y2)") (class "Default")
      (node (ref "IC3") (pin "16") (pinfunction "1Y2_16") (pintype "bidirectional"))
      (node (ref "JP42") (pin "1") (pinfunction "1_1") (pintype "passive"))
    )
    (net (code "37") (name "Net-(IC3-1Y3)") (class "Default")
      (node (ref "IC3") (pin "14") (pinfunction "1Y3_14") (pintype "bidirectional"))
      (node (ref "JP44") (pin "1") (pinfunction "1_1") (pintype "passive"))
    )
    (net (code "38") (name "Net-(IC3-1Y4)") (class "Default")
      (node (ref "IC3") (pin "12") (pinfunction "1Y4_12") (pintype "bidirectional"))
      (node (ref "JP48") (pin "1") (pinfunction "1_1") (pintype "passive"))
    )
    (net (code "39") (name "Net-(IC3-2Y1)") (class "Default")
      (node (ref "IC3") (pin "9") (pinfunction "2Y1_9") (pintype "bidirectional"))
      (node (ref "JP58") (pin "1") (pinfunction "1_1") (pintype "passive"))
    )
    (net (code "40") (name "Net-(IC3-2Y2)") (class "Default")
      (node (ref "IC3") (pin "7") (pinfunction "2Y2_7") (pintype "bidirectional"))
      (node (ref "JP54") (pin "1") (pinfunction "1_1") (pintype "passive"))
    )
    (net (code "41") (name "Net-(IC3-2Y3)") (class "Default")
      (node (ref "IC3") (pin "5") (pinfunction "2Y3_5") (pintype "bidirectional"))
      (node (ref "JP52") (pin "1") (pinfunction "1_1") (pintype "passive"))
    )
    (net (code "42") (name "Net-(IC3-2Y4)") (class "Default")
      (node (ref "IC3") (pin "3") (pinfunction "2Y4_3") (pintype "bidirectional"))
      (node (ref "JP50") (pin "1") (pinfunction "1_1") (pintype "passive"))
    )
    (net (code "43") (name "Net-(IC4-1Y1)") (class "Default")
      (node (ref "IC4") (pin "18") (pinfunction "1Y1_18") (pintype "bidirectional"))
      (node (ref "JP22") (pin "1") (pinfunction "1_1") (pintype "passive"))
    )
    (net (code "44") (name "Net-(IC4-1Y2)") (class "Default")
      (node (ref "IC4") (pin "16") (pinfunction "1Y2_16") (pintype "bidirectional"))
      (node (ref "JP24") (pin "1") (pinfunction "1_1") (pintype "passive"))
    )
    (net (code "45") (name "Net-(IC4-1Y3)") (class "Default")
      (node (ref "IC4") (pin "14") (pinfunction "1Y3_14") (pintype "bidirectional"))
      (node (ref "JP26") (pin "1") (pinfunction "1_1") (pintype "passive"))
    )
    (net (code "46") (name "Net-(IC4-1Y4)") (class "Default")
      (node (ref "IC4") (pin "12") (pinfunction "1Y4_12") (pintype "bidirectional"))
      (node (ref "JP28") (pin "1") (pinfunction "1_1") (pintype "passive"))
    )
    (net (code "47") (name "Net-(IC4-2Y1)") (class "Default")
      (node (ref "IC4") (pin "9") (pinfunction "2Y1_9") (pintype "bidirectional"))
      (node (ref "JP36") (pin "1") (pinfunction "1_1") (pintype "passive"))
    )
    (net (code "48") (name "Net-(IC4-2Y2)") (class "Default")
      (node (ref "IC4") (pin "7") (pinfunction "2Y2_7") (pintype "bidirectional"))
      (node (ref "JP34") (pin "1") (pinfunction "1_1") (pintype "passive"))
    )
    (net (code "49") (name "Net-(IC4-2Y3)") (class "Default")
      (node (ref "IC4") (pin "5") (pinfunction "2Y3_5") (pintype "bidirectional"))
      (node (ref "JP32") (pin "1") (pinfunction "1_1") (pintype "passive"))
    )
    (net (code "50") (name "Net-(IC4-2Y4)") (class "Default")
      (node (ref "IC4") (pin "3") (pinfunction "2Y4_3") (pintype "bidirectional"))
      (node (ref "JP30") (pin "1") (pinfunction "1_1") (pintype "passive"))
    )
    (net (code "51") (name "Net-(IC5-1Y1)") (class "Default")
      (node (ref "IC5") (pin "18") (pinfunction "1Y1_18") (pintype "bidirectional"))
      (node (ref "JP4") (pin "1") (pinfunction "1_1") (pintype "passive"))
    )
    (net (code "52") (name "Net-(IC5-1Y2)") (class "Default")
      (node (ref "IC5") (pin "16") (pinfunction "1Y2_16") (pintype "bidirectional"))
      (node (ref "JP6") (pin "1") (pinfunction "1_1") (pintype "passive"))
    )
    (net (code "53") (name "Net-(IC5-1Y3)") (class "Default")
      (node (ref "IC5") (pin "14") (pinfunction "1Y3_14") (pintype "bidirectional"))
      (node (ref "JP8") (pin "1") (pinfunction "1_1") (pintype "passive"))
    )
    (net (code "54") (name "Net-(IC5-1Y4)") (class "Default")
      (node (ref "IC5") (pin "12") (pinfunction "1Y4_12") (pintype "bidirectional"))
      (node (ref "JP10") (pin "1") (pinfunction "1_1") (pintype "passive"))
    )
    (net (code "55") (name "Net-(IC5-2Y1)") (class "Default")
      (node (ref "IC5") (pin "9") (pinfunction "2Y1_9") (pintype "bidirectional"))
      (node (ref "JP18") (pin "1") (pinfunction "1_1") (pintype "passive"))
    )
    (net (code "56") (name "Net-(IC5-2Y2)") (class "Default")
      (node (ref "IC5") (pin "7") (pinfunction "2Y2_7") (pintype "bidirectional"))
      (node (ref "JP16") (pin "1") (pinfunction "1_1") (pintype "passive"))
    )
    (net (code "57") (name "Net-(IC5-2Y3)") (class "Default")
      (node (ref "IC5") (pin "5") (pinfunction "2Y3_5") (pintype "bidirectional"))
      (node (ref "JP14") (pin "1") (pinfunction "1_1") (pintype "passive"))
    )
    (net (code "58") (name "Net-(IC5-2Y4)") (class "Default")
      (node (ref "IC5") (pin "3") (pinfunction "2Y4_3") (pintype "bidirectional"))
      (node (ref "JP12") (pin "1") (pinfunction "1_1") (pintype "passive"))
    )
    (net (code "59") (name "Net-(IC6-1Y1)") (class "Default")
      (node (ref "IC6") (pin "18") (pinfunction "1Y1_18") (pintype "bidirectional"))
      (node (ref "JP1") (pin "1") (pinfunction "1_1") (pintype "passive"))
    )
    (net (code "60") (name "Net-(IC6-1Y2)") (class "Default")
      (node (ref "IC6") (pin "16") (pinfunction "1Y2_16") (pintype "bidirectional"))
      (node (ref "JP19") (pin "1") (pinfunction "1_1") (pintype "passive"))
    )
    (net (code "61") (name "Net-(IC6-1Y3)") (class "Default")
      (node (ref "IC6") (pin "14") (pinfunction "1Y3_14") (pintype "bidirectional"))
      (node (ref "JP37") (pin "1") (pinfunction "1_1") (pintype "passive"))
    )
    (net (code "62") (name "Net-(IC6-1Y4)") (class "Default")
      (node (ref "IC6") (pin "12") (pinfunction "1Y4_12") (pintype "bidirectional"))
      (node (ref "JP46") (pin "1") (pinfunction "1_1") (pintype "passive"))
    )
    (net (code "63") (name "Net-(IC6-2Y1)") (class "Default")
      (node (ref "IC6") (pin "9") (pinfunction "2Y1_9") (pintype "bidirectional"))
      (node (ref "JP55") (pin "1") (pinfunction "1_1") (pintype "passive"))
    )
    (net (code "64") (name "Net-(IC6-2Y2)") (class "Default")
      (node (ref "IC6") (pin "7") (pinfunction "2Y2_7") (pintype "bidirectional"))
      (node (ref "JP64") (pin "1") (pinfunction "1_1") (pintype "passive"))
    )
    (net (code "65") (name "Net-(IC6-2Y3)") (class "Default")
      (node (ref "IC6") (pin "5") (pinfunction "2Y3_5") (pintype "bidirectional"))
      (node (ref "JP73") (pin "1") (pinfunction "1_1") (pintype "passive"))
    )
    (net (code "66") (name "Net-(IC6-2Y4)") (class "Default")
      (node (ref "IC6") (pin "3") (pinfunction "2Y4_3") (pintype "bidirectional"))
      (node (ref "JP82") (pin "1") (pinfunction "1_1") (pintype "passive"))
    )
    (net (code "67") (name "Net-(IC7-1Y1)") (class "Default")
      (node (ref "IC7") (pin "18") (pinfunction "1Y1_18") (pintype "bidirectional"))
      (node (ref "JP39") (pin "1") (pinfunction "1_1") (pintype "passive"))
    )
    (net (code "68") (name "Net-(IC7-1Y2)") (class "Default")
      (node (ref "IC7") (pin "16") (pinfunction "1Y2_16") (pintype "bidirectional"))
      (node (ref "JP41") (pin "1") (pinfunction "1_1") (pintype "passive"))
    )
    (net (code "69") (name "Net-(IC7-1Y3)") (class "Default")
      (node (ref "IC7") (pin "14") (pinfunction "1Y3_14") (pintype "bidirectional"))
      (node (ref "JP43") (pin "1") (pinfunction "1_1") (pintype "passive"))
    )
    (net (code "70") (name "Net-(IC7-1Y4)") (class "Default")
      (node (ref "IC7") (pin "12") (pinfunction "1Y4_12") (pintype "bidirectional"))
      (node (ref "JP45") (pin "1") (pinfunction "1_1") (pintype "passive"))
    )
    (net (code "71") (name "Net-(IC7-2Y1)") (class "Default")
      (node (ref "IC7") (pin "9") (pinfunction "2Y1_9") (pintype "bidirectional"))
      (node (ref "JP49") (pin "1") (pinfunction "1_1") (pintype "passive"))
    )
    (net (code "72") (name "Net-(IC7-2Y2)") (class "Default")
      (node (ref "IC7") (pin "7") (pinfunction "2Y2_7") (pintype "bidirectional"))
      (node (ref "JP51") (pin "1") (pinfunction "1_1") (pintype "passive"))
    )
    (net (code "73") (name "Net-(IC7-2Y3)") (class "Default")
      (node (ref "IC7") (pin "5") (pinfunction "2Y3_5") (pintype "bidirectional"))
      (node (ref "JP53") (pin "1") (pinfunction "1_1") (pintype "passive"))
    )
    (net (code "74") (name "Net-(IC7-2Y4)") (class "Default")
      (node (ref "IC7") (pin "3") (pinfunction "2Y4_3") (pintype "bidirectional"))
      (node (ref "JP57") (pin "1") (pinfunction "1_1") (pintype "passive"))
    )
    (net (code "75") (name "Net-(IC8-1Y1)") (class "Default")
      (node (ref "IC8") (pin "18") (pinfunction "1Y1_18") (pintype "bidirectional"))
      (node (ref "JP21") (pin "1") (pinfunction "1_1") (pintype "passive"))
    )
    (net (code "76") (name "Net-(IC8-1Y2)") (class "Default")
      (node (ref "IC8") (pin "16") (pinfunction "1Y2_16") (pintype "bidirectional"))
      (node (ref "JP23") (pin "1") (pinfunction "1_1") (pintype "passive"))
    )
    (net (code "77") (name "Net-(IC8-1Y3)") (class "Default")
      (node (ref "IC8") (pin "14") (pinfunction "1Y3_14") (pintype "bidirectional"))
      (node (ref "JP25") (pin "1") (pinfunction "1_1") (pintype "passive"))
    )
    (net (code "78") (name "Net-(IC8-1Y4)") (class "Default")
      (node (ref "IC8") (pin "12") (pinfunction "1Y4_12") (pintype "bidirectional"))
      (node (ref "JP27") (pin "1") (pinfunction "1_1") (pintype "passive"))
    )
    (net (code "79") (name "Net-(IC8-2Y1)") (class "Default")
      (node (ref "IC8") (pin "9") (pinfunction "2Y1_9") (pintype "bidirectional"))
      (node (ref "JP29") (pin "1") (pinfunction "1_1") (pintype "passive"))
    )
    (net (code "80") (name "Net-(IC8-2Y2)") (class "Default")
      (node (ref "IC8") (pin "7") (pinfunction "2Y2_7") (pintype "bidirectional"))
      (node (ref "JP31") (pin "1") (pinfunction "1_1") (pintype "passive"))
    )
    (net (code "81") (name "Net-(IC8-2Y3)") (class "Default")
      (node (ref "IC8") (pin "5") (pinfunction "2Y3_5") (pintype "bidirectional"))
      (node (ref "JP33") (pin "1") (pinfunction "1_1") (pintype "passive"))
    )
    (net (code "82") (name "Net-(IC8-2Y4)") (class "Default")
      (node (ref "IC8") (pin "3") (pinfunction "2Y4_3") (pintype "bidirectional"))
      (node (ref "JP35") (pin "1") (pinfunction "1_1") (pintype "passive"))
    )
    (net (code "83") (name "Net-(IC9-1Y1)") (class "Default")
      (node (ref "IC9") (pin "18") (pinfunction "1Y1_18") (pintype "bidirectional"))
      (node (ref "JP3") (pin "1") (pinfunction "1_1") (pintype "passive"))
    )
    (net (code "84") (name "Net-(IC9-1Y2)") (class "Default")
      (node (ref "IC9") (pin "16") (pinfunction "1Y2_16") (pintype "bidirectional"))
      (node (ref "JP5") (pin "1") (pinfunction "1_1") (pintype "passive"))
    )
    (net (code "85") (name "Net-(IC9-1Y3)") (class "Default")
      (node (ref "IC9") (pin "14") (pinfunction "1Y3_14") (pintype "bidirectional"))
      (node (ref "JP7") (pin "1") (pinfunction "1_1") (pintype "passive"))
    )
    (net (code "86") (name "Net-(IC9-1Y4)") (class "Default")
      (node (ref "IC9") (pin "12") (pinfunction "1Y4_12") (pintype "bidirectional"))
      (node (ref "JP9") (pin "1") (pinfunction "1_1") (pintype "passive"))
    )
    (net (code "87") (name "Net-(IC9-2Y1)") (class "Default")
      (node (ref "IC9") (pin "9") (pinfunction "2Y1_9") (pintype "bidirectional"))
      (node (ref "JP11") (pin "1") (pinfunction "1_1") (pintype "passive"))
    )
    (net (code "88") (name "Net-(IC9-2Y2)") (class "Default")
      (node (ref "IC9") (pin "7") (pinfunction "2Y2_7") (pintype "bidirectional"))
      (node (ref "JP13") (pin "1") (pinfunction "1_1") (pintype "passive"))
    )
    (net (code "89") (name "Net-(IC9-2Y3)") (class "Default")
      (node (ref "IC9") (pin "5") (pinfunction "2Y3_5") (pintype "bidirectional"))
      (node (ref "JP15") (pin "1") (pinfunction "1_1") (pintype "passive"))
    )
    (net (code "90") (name "Net-(IC9-2Y4)") (class "Default")
      (node (ref "IC9") (pin "3") (pinfunction "2Y4_3") (pintype "bidirectional"))
      (node (ref "JP17") (pin "1") (pinfunction "1_1") (pintype "passive"))
    )
    (net (code "91") (name "Net-(IC10-1Y1)") (class "Default")
      (node (ref "IC10") (pin "18") (pinfunction "1Y1_18") (pintype "bidirectional"))
      (node (ref "JP2") (pin "1") (pinfunction "1_1") (pintype "passive"))
    )
    (net (code "92") (name "Net-(IC10-1Y2)") (class "Default")
      (node (ref "IC10") (pin "16") (pinfunction "1Y2_16") (pintype "bidirectional"))
      (node (ref "JP20") (pin "1") (pinfunction "1_1") (pintype "passive"))
    )
    (net (code "93") (name "Net-(IC10-1Y3)") (class "Default")
      (node (ref "IC10") (pin "14") (pinfunction "1Y3_14") (pintype "bidirectional"))
      (node (ref "JP38") (pin "1") (pinfunction "1_1") (pintype "passive"))
    )
    (net (code "94") (name "Net-(IC10-1Y4)") (class "Default")
      (node (ref "IC10") (pin "12") (pinfunction "1Y4_12") (pintype "bidirectional"))
      (node (ref "JP47") (pin "1") (pinfunction "1_1") (pintype "passive"))
    )
    (net (code "95") (name "Net-(IC10-2Y1)") (class "Default")
      (node (ref "IC10") (pin "9") (pinfunction "2Y1_9") (pintype "bidirectional"))
      (node (ref "JP83") (pin "1") (pinfunction "1_1") (pintype "passive"))
    )
    (net (code "96") (name "Net-(IC10-2Y2)") (class "Default")
      (node (ref "IC10") (pin "7") (pinfunction "2Y2_7") (pintype "bidirectional"))
      (node (ref "JP74") (pin "1") (pinfunction "1_1") (pintype "passive"))
    )
    (net (code "97") (name "Net-(IC10-2Y3)") (class "Default")
      (node (ref "IC10") (pin "5") (pinfunction "2Y3_5") (pintype "bidirectional"))
      (node (ref "JP65") (pin "1") (pinfunction "1_1") (pintype "passive"))
    )
    (net (code "98") (name "Net-(IC10-2Y4)") (class "Default")
      (node (ref "IC10") (pin "3") (pinfunction "2Y4_3") (pintype "bidirectional"))
      (node (ref "JP56") (pin "1") (pinfunction "1_1") (pintype "passive"))
    )
    (net (code "99") (name "Net-(IC11-2Y)") (class "Default")
      (node (ref "IC11") (pin "4") (pinfunction "2Y_4") (pintype "bidirectional"))
      (node (ref "J1") (pin "5") (pinfunction "CLK_5") (pintype "bidirectional"))
    )
    (net (code "100") (name "Net-(IC11-3Y)") (class "Default")
      (node (ref "IC11") (pin "6") (pinfunction "3Y_6") (pintype "bidirectional"))
      (node (ref "J1") (pin "3") (pinfunction "CMD_3") (pintype "bidirectional"))
    )
    (net (code "101") (name "Net-(IC11-4Y)") (class "Default")
      (node (ref "IC11") (pin "10") (pinfunction "4Y_10") (pintype "bidirectional"))
      (node (ref "J1") (pin "2") (pinfunction "CD/DAT3_2") (pintype "bidirectional"))
    )
    (net (code "102") (name "Net-(Q9-D)") (class "Default")
      (node (ref "Q9") (pin "2") (pinfunction "D_2") (pintype "bidirectional"))
      (node (ref "R4") (pin "2") (pinfunction "2_2") (pintype "passive"))
    )
    (net (code "103") (name "Net-(Q9-S)") (class "Default")
      (node (ref "L_1_2") (pin "1") (pinfunction "1_1") (pintype "bidirectional"))
      (node (ref "Q9") (pin "3") (pinfunction "S_3") (pintype "bidirectional"))
    )
    (net (code "104") (name "Net-(Q10-D)") (class "Default")
      (node (ref "Q10") (pin "2") (pinfunction "D_2") (pintype "bidirectional"))
      (node (ref "R5") (pin "2") (pinfunction "2_2") (pintype "passive"))
    )
    (net (code "105") (name "Net-(Q10-S)") (class "Default")
      (node (ref "L_7_8") (pin "2") (pinfunction "2_2") (pintype "bidirectional"))
      (node (ref "Q10") (pin "3") (pinfunction "S_3") (pintype "bidirectional"))
    )
    (net (code "106") (name "Net-(Q11-D)") (class "Default")
      (node (ref "Q11") (pin "2") (pinfunction "D_2") (pintype "bidirectional"))
      (node (ref "R3") (pin "2") (pinfunction "2_2") (pintype "passive"))
    )
    (net (code "107") (name "Net-(Q11-S)") (class "Default")
      (node (ref "L_1_2") (pin "2") (pinfunction "2_2") (pintype "bidirectional"))
      (node (ref "Q11") (pin "3") (pinfunction "S_3") (pintype "bidirectional"))
    )
    (net (code "108") (name "Net-(Q12-D)") (class "Default")
      (node (ref "Q12") (pin "2") (pinfunction "D_2") (pintype "bidirectional"))
      (node (ref "R8") (pin "2") (pinfunction "2_2") (pintype "passive"))
    )
    (net (code "109") (name "Net-(Q12-S)") (class "Default")
      (node (ref "L_3_4") (pin "1") (pinfunction "1_1") (pintype "bidirectional"))
      (node (ref "Q12") (pin "3") (pinfunction "S_3") (pintype "bidirectional"))
    )
    (net (code "110") (name "Net-(Q13-D)") (class "Default")
      (node (ref "Q13") (pin "2") (pinfunction "D_2") (pintype "bidirectional"))
      (node (ref "R6") (pin "2") (pinfunction "2_2") (pintype "passive"))
    )
    (net (code "111") (name "Net-(Q13-S)") (class "Default")
      (node (ref "L_7_8") (pin "1") (pinfunction "1_1") (pintype "bidirectional"))
      (node (ref "Q13") (pin "3") (pinfunction "S_3") (pintype "bidirectional"))
    )
    (net (code "112") (name "Net-(Q14-D)") (class "Default")
      (node (ref "Q14") (pin "2") (pinfunction "D_2") (pintype "bidirectional"))
      (node (ref "R1") (pin "2") (pinfunction "2_2") (pintype "passive"))
    )
    (net (code "113") (name "Net-(Q14-S)") (class "Default")
      (node (ref "L_5_6") (pin "2") (pinfunction "2_2") (pintype "bidirectional"))
      (node (ref "Q14") (pin "3") (pinfunction "S_3") (pintype "bidirectional"))
    )
    (net (code "114") (name "Net-(Q15-D)") (class "Default")
      (node (ref "Q15") (pin "2") (pinfunction "D_2") (pintype "bidirectional"))
      (node (ref "R2") (pin "2") (pinfunction "2_2") (pintype "passive"))
    )
    (net (code "115") (name "Net-(Q15-S)") (class "Default")
      (node (ref "L_5_6") (pin "1") (pinfunction "1_1") (pintype "bidirectional"))
      (node (ref "Q15") (pin "3") (pinfunction "S_3") (pintype "bidirectional"))
    )
    (net (code "116") (name "Net-(Q16-D)") (class "Default")
      (node (ref "Q16") (pin "2") (pinfunction "D_2") (pintype "bidirectional"))
      (node (ref "R7") (pin "2") (pinfunction "2_2") (pintype "passive"))
    )
    (net (code "117") (name "Net-(Q16-S)") (class "Default")
      (node (ref "L_3_4") (pin "2") (pinfunction "2_2") (pintype "bidirectional"))
      (node (ref "Q16") (pin "3") (pinfunction "S_3") (pintype "bidirectional"))
    )
    (net (code "118") (name "Y1") (class "Default")
      (node (ref "IC10") (pin "2") (pinfunction "1A1_2") (pintype "bidirectional"))
      (node (ref "IC2") (pin "15") (pinfunction "Y0_15") (pintype "bidirectional"))
      (node (ref "IC3") (pin "2") (pinfunction "1A1_2") (pintype "bidirectional"))
      (node (ref "IC4") (pin "2") (pinfunction "1A1_2") (pintype "bidirectional"))
      (node (ref "IC5") (pin "2") (pinfunction "1A1_2") (pintype "bidirectional"))
      (node (ref "IC6") (pin "2") (pinfunction "1A1_2") (pintype "bidirectional"))
      (node (ref "IC7") (pin "2") (pinfunction "1A1_2") (pintype "bidirectional"))
      (node (ref "IC8") (pin "2") (pinfunction "1A1_2") (pintype "bidirectional"))
      (node (ref "IC9") (pin "2") (pinfunction "1A1_2") (pintype "bidirectional"))
    )
    (net (code "119") (name "Y2") (class "Default")
      (node (ref "IC10") (pin "4") (pinfunction "1A2_4") (pintype "bidirectional"))
      (node (ref "IC2") (pin "14") (pinfunction "Y1_14") (pintype "bidirectional"))
      (node (ref "IC3") (pin "4") (pinfunction "1A2_4") (pintype "bidirectional"))
      (node (ref "IC4") (pin "4") (pinfunction "1A2_4") (pintype "bidirectional"))
      (node (ref "IC5") (pin "4") (pinfunction "1A2_4") (pintype "bidirectional"))
      (node (ref "IC6") (pin "4") (pinfunction "1A2_4") (pintype "bidirectional"))
      (node (ref "IC7") (pin "4") (pinfunction "1A2_4") (pintype "bidirectional"))
      (node (ref "IC8") (pin "4") (pinfunction "1A2_4") (pintype "bidirectional"))
      (node (ref "IC9") (pin "4") (pinfunction "1A2_4") (pintype "bidirectional"))
    )
    (net (code "120") (name "Y3") (class "Default")
      (node (ref "IC10") (pin "6") (pinfunction "1A3_6") (pintype "bidirectional"))
      (node (ref "IC2") (pin "13") (pinfunction "Y2_13") (pintype "bidirectional"))
      (node (ref "IC3") (pin "6") (pinfunction "1A3_6") (pintype "bidirectional"))
      (node (ref "IC4") (pin "6") (pinfunction "1A3_6") (pintype "bidirectional"))
      (node (ref "IC5") (pin "6") (pinfunction "1A3_6") (pintype "bidirectional"))
      (node (ref "IC6") (pin "6") (pinfunction "1A3_6") (pintype "bidirectional"))
      (node (ref "IC7") (pin "6") (pinfunction "1A3_6") (pintype "bidirectional"))
      (node (ref "IC8") (pin "6") (pinfunction "1A3_6") (pintype "bidirectional"))
      (node (ref "IC9") (pin "6") (pinfunction "1A3_6") (pintype "bidirectional"))
    )
    (net (code "121") (name "Y4") (class "Default")
      (node (ref "IC10") (pin "8") (pinfunction "1A4_8") (pintype "bidirectional"))
      (node (ref "IC2") (pin "12") (pinfunction "Y3_12") (pintype "bidirectional"))
      (node (ref "IC3") (pin "8") (pinfunction "1A4_8") (pintype "bidirectional"))
      (node (ref "IC4") (pin "8") (pinfunction "1A4_8") (pintype "bidirectional"))
      (node (ref "IC5") (pin "8") (pinfunction "1A4_8") (pintype "bidirectional"))
      (node (ref "IC6") (pin "8") (pinfunction "1A4_8") (pintype "bidirectional"))
      (node (ref "IC7") (pin "8") (pinfunction "1A4_8") (pintype "bidirectional"))
      (node (ref "IC8") (pin "8") (pinfunction "1A4_8") (pintype "bidirectional"))
      (node (ref "IC9") (pin "8") (pinfunction "1A4_8") (pintype "bidirectional"))
    )
    (net (code "122") (name "Y5") (class "Default")
      (node (ref "IC10") (pin "17") (pinfunction "2A4_17") (pintype "bidirectional"))
      (node (ref "IC2") (pin "11") (pinfunction "Y4_11") (pintype "bidirectional"))
      (node (ref "IC3") (pin "17") (pinfunction "2A4_17") (pintype "bidirectional"))
      (node (ref "IC4") (pin "17") (pinfunction "2A4_17") (pintype "bidirectional"))
      (node (ref "IC5") (pin "17") (pinfunction "2A4_17") (pintype "bidirectional"))
      (node (ref "IC6") (pin "11") (pinfunction "2A1_11") (pintype "bidirectional"))
      (node (ref "IC7") (pin "11") (pinfunction "2A1_11") (pintype "bidirectional"))
      (node (ref "IC8") (pin "11") (pinfunction "2A1_11") (pintype "bidirectional"))
      (node (ref "IC9") (pin "11") (pinfunction "2A1_11") (pintype "bidirectional"))
    )
    (net (code "123") (name "Y6") (class "Default")
      (node (ref "IC10") (pin "15") (pinfunction "2A3_15") (pintype "bidirectional"))
      (node (ref "IC2") (pin "10") (pinfunction "Y5_10") (pintype "bidirectional"))
      (node (ref "IC3") (pin "15") (pinfunction "2A3_15") (pintype "bidirectional"))
      (node (ref "IC4") (pin "15") (pinfunction "2A3_15") (pintype "bidirectional"))
      (node (ref "IC5") (pin "15") (pinfunction "2A3_15") (pintype "bidirectional"))
      (node (ref "IC6") (pin "13") (pinfunction "2A2_13") (pintype "bidirectional"))
      (node (ref "IC7") (pin "13") (pinfunction "2A2_13") (pintype "bidirectional"))
      (node (ref "IC8") (pin "13") (pinfunction "2A2_13") (pintype "bidirectional"))
      (node (ref "IC9") (pin "13") (pinfunction "2A2_13") (pintype "bidirectional"))
    )
    (net (code "124") (name "Y7") (class "Default")
      (node (ref "IC10") (pin "13") (pinfunction "2A2_13") (pintype "bidirectional"))
      (node (ref "IC2") (pin "9") (pinfunction "Y6_9") (pintype "bidirectional"))
      (node (ref "IC3") (pin "13") (pinfunction "2A2_13") (pintype "bidirectional"))
      (node (ref "IC4") (pin "13") (pinfunction "2A2_13") (pintype "bidirectional"))
      (node (ref "IC5") (pin "13") (pinfunction "2A2_13") (pintype "bidirectional"))
      (node (ref "IC6") (pin "15") (pinfunction "2A3_15") (pintype "bidirectional"))
      (node (ref "IC7") (pin "15") (pinfunction "2A3_15") (pintype "bidirectional"))
      (node (ref "IC8") (pin "15") (pinfunction "2A3_15") (pintype "bidirectional"))
      (node (ref "IC9") (pin "15") (pinfunction "2A3_15") (pintype "bidirectional"))
    )
    (net (code "125") (name "Y8") (class "Default")
      (node (ref "IC10") (pin "11") (pinfunction "2A1_11") (pintype "bidirectional"))
      (node (ref "IC2") (pin "7") (pinfunction "Y7_7") (pintype "bidirectional"))
      (node (ref "IC3") (pin "11") (pinfunction "2A1_11") (pintype "bidirectional"))
      (node (ref "IC4") (pin "11") (pinfunction "2A1_11") (pintype "bidirectional"))
      (node (ref "IC5") (pin "11") (pinfunction "2A1_11") (pintype "bidirectional"))
      (node (ref "IC6") (pin "17") (pinfunction "2A4_17") (pintype "bidirectional"))
      (node (ref "IC7") (pin "17") (pinfunction "2A4_17") (pintype "bidirectional"))
      (node (ref "IC8") (pin "17") (pinfunction "2A4_17") (pintype "bidirectional"))
      (node (ref "IC9") (pin "17") (pinfunction "2A4_17") (pintype "bidirectional"))
    )
    (net (code "126") (name "Z0") (class "Default")
      (node (ref "IC12") (pin "3") (pinfunction "C_3") (pintype "input"))
      (node (ref "U$2") (pin "D8") (pinfunction "D8_D8") (pintype "bidirectional"))
    )
    (net (code "127") (name "Z1") (class "Default")
      (node (ref "IC12") (pin "2") (pinfunction "B_2") (pintype "input"))
      (node (ref "U$2") (pin "D7") (pinfunction "D7_D7") (pintype "bidirectional"))
    )
    (net (code "128") (name "Z2") (class "Default")
      (node (ref "IC12") (pin "1") (pinfunction "A_1") (pintype "input"))
      (node (ref "U$2") (pin "D6") (pinfunction "D6_D6") (pintype "bidirectional"))
    )
    (net (code "129") (name "unconnected-(IC11-1Y-Pad2)") (class "Default")
      (node (ref "IC11") (pin "2") (pinfunction "1Y_2") (pintype "bidirectional"))
    )
    (net (code "130") (name "unconnected-(IC11-5Y-Pad12)") (class "Default")
      (node (ref "IC11") (pin "12") (pinfunction "5Y_12") (pintype "bidirectional"))
    )
    (net (code "131") (name "unconnected-(IC11-6Y-Pad15)") (class "Default")
      (node (ref "IC11") (pin "15") (pinfunction "6Y_15") (pintype "bidirectional"))
    )
    (net (code "132") (name "unconnected-(IC11-NC-Pad16)") (class "Default")
      (node (ref "IC11") (pin "16") (pinfunction "NC_16") (pintype "no_connect"))
    )
    (net (code "133") (name "unconnected-(IC11-NC_2-Pad13)") (class "Default")
      (node (ref "IC11") (pin "13") (pinfunction "NC_2_13") (pintype "bidirectional"))
    )
    (net (code "134") (name "unconnected-(U$2-PadAREF)") (class "Default")
      (node (ref "U$2") (pin "AREF") (pinfunction "AREF_AREF") (pintype "bidirectional"))
    )
    (net (code "135") (name "unconnected-(U$2-{slash}RESET-PadRESET)") (class "Default")
      (node (ref "U$2") (pin "RESET") (pinfunction "/RESET_RESET") (pintype "bidirectional"))
    )
  )
)
